# Power_5V_77V.net
KiCad netlist of a schematic drawn in EAGLE
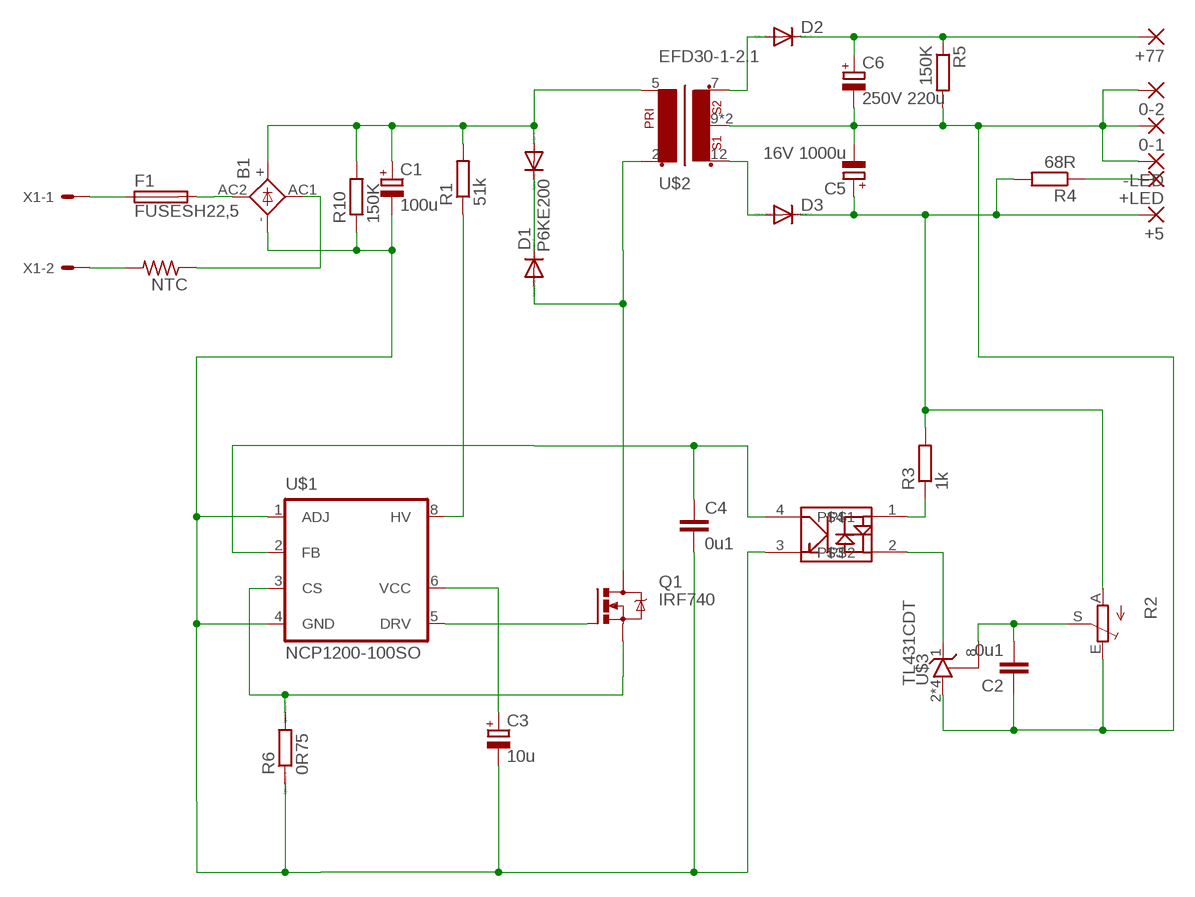
[diagram p0: schematic, sheet 1]

(export (version "E")
  (design (tool "Eeschema 10.0.6"))
  (components
    (comp (ref "+5")
      (value "2,54/0,8")
      (footprint "eagle-import:2,54_0,8")
      (libsource (lib "eagle-import") (part "2,54/0,8"))
    )
    (comp (ref "+77")
      (value "3,17/1,1")
      (footprint "eagle-import:3,17_1,1")
      (libsource (lib "eagle-import") (part "3,17/1,1"))
    )
    (comp (ref "+LED")
      (value "2,54/0,8")
      (footprint "eagle-import:2,54_0,8")
      (libsource (lib "eagle-import") (part "2,54/0,8"))
    )
    (comp (ref "-LED")
      (value "2,54/0,8")
      (footprint "eagle-import:2,54_0,8")
      (libsource (lib "eagle-import") (part "2,54/0,8"))
    )
    (comp (ref "0-1")
      (value "2,54/0,8")
      (footprint "eagle-import:2,54_0,8")
      (libsource (lib "eagle-import") (part "2,54/0,8"))
    )
    (comp (ref "0-2")
      (value "3,17/1,1")
      (footprint "eagle-import:3,17_1,1")
      (libsource (lib "eagle-import") (part "3,17/1,1"))
    )
    (comp (ref "B1")
      (value "KBL")
      (footprint "eagle-import:KBL")
      (libsource (lib "eagle-import") (part "KBL"))
    )
    (comp (ref "C1")
      (value "100u")
      (footprint "eagle-import:EB25D")
      (libsource (lib "eagle-import") (part "CPOL-EUE10-25"))
    )
    (comp (ref "C2")
      (value "0u1")
      (footprint "eagle-import:C1206")
      (libsource (lib "eagle-import") (part "C-EUC1206"))
    )
    (comp (ref "C3")
      (value "10u")
      (footprint "eagle-import:E2,5-5")
      (libsource (lib "eagle-import") (part "CPOL-EUE2.5-5"))
    )
    (comp (ref "C4")
      (value "0u1")
      (footprint "eagle-import:C1206")
      (libsource (lib "eagle-import") (part "C-EUC1206"))
    )
    (comp (ref "C5")
      (value "16V 1000u")
      (footprint "eagle-import:E3,5-8")
      (libsource (lib "eagle-import") (part "CPOL-EUE3.5-8"))
    )
    (comp (ref "C6")
      (value "250V 220u")
      (footprint "eagle-import:EB22,5D")
      (libsource (lib "eagle-import") (part "CPOL-EUE10-22.5"))
    )
    (comp (ref "D1")
      (value "DIODE-DO-214AC")
      (footprint "eagle-import:DO-214AC")
      (libsource (lib "eagle-import") (part "DIODE-DO-214AC"))
    )
    (comp (ref "D2")
      (value "DIODE-TO220V")
      (footprint "eagle-import:TO220ACS")
      (libsource (lib "eagle-import") (part "DIODE-TO220V"))
    )
    (comp (ref "D3")
      (value "DIODE-SMB")
      (footprint "eagle-import:SMB")
      (libsource (lib "eagle-import") (part "DIODE-SMB"))
    )
    (comp (ref "F1")
      (value "FUSESH22,5")
      (footprint "eagle-import:SH22,5")
      (fields (field (name "MF") "SCHURTER") (field (name "MPN") "0031.8201"))
      (libsource (lib "eagle-import") (part "SH22,5"))
    )
    (comp (ref "NTC")
      (value "R-US_0207/10")
      (footprint "eagle-import:0207_10")
      (libsource (lib "eagle-import") (part "R-US_0207/10"))
    )
    (comp (ref "P6KE200")
      (value "DIODE-SMB")
      (footprint "eagle-import:SMB")
      (libsource (lib "eagle-import") (part "DIODE-SMB"))
    )
    (comp (ref "Q1")
      (value "IRF740")
      (footprint "eagle-import:TO220BV")
      (libsource (lib "eagle-import") (part "IRF740"))
    )
    (comp (ref "R1")
      (value "51k")
      (footprint "eagle-import:0922_22")
      (libsource (lib "eagle-import") (part "R-EU_0922/22"))
    )
    (comp (ref "R2")
      (value "TRIM_EU-S75H")
      (footprint "eagle-import:S75H")
      (libsource (lib "eagle-import") (part "TRIM_EU-S75H"))
    )
    (comp (ref "R3")
      (value "1k")
      (footprint "eagle-import:R1206")
      (libsource (lib "eagle-import") (part "R-EU_R1206"))
    )
    (comp (ref "R4")
      (value "68R")
      (footprint "eagle-import:R1206")
      (libsource (lib "eagle-import") (part "R-EU_R1206"))
    )
    (comp (ref "R5")
      (value "150K")
      (footprint "eagle-import:R1206")
      (libsource (lib "eagle-import") (part "R-EU_R1206"))
    )
    (comp (ref "R6")
      (value "0R75")
      (footprint "eagle-import:0411_15")
      (libsource (lib "eagle-import") (part "R-EU_0411_15"))
    )
    (comp (ref "R10")
      (value "150K")
      (footprint "eagle-import:0207_10")
      (libsource (lib "eagle-import") (part "R-EU_0207/10"))
    )
    (comp (ref "U$1")
      (value "NCP1200-100SO")
      (footprint "eagle-import:SOP8")
      (libsource (lib "eagle-import") (part "NCP1200-100SO"))
    )
    (comp (ref "U$2")
      (value "EFD30-1-2.1")
      (footprint "eagle-import:EFD30_1-2.1")
      (libsource (lib "eagle-import") (part "EFD30-1-2.1"))
    )
    (comp (ref "U$3")
      (value "TL431CDT")
      (footprint "eagle-import:SO8")
      (libsource (lib "eagle-import") (part "TL431CDT"))
    )
    (comp (ref "U$5")
      (value "EL3H4(TA)-VG")
      (footprint "eagle-import:SSOP4")
      (libsource (lib "eagle-import") (part "EL3H4(TA)-VG"))
    )
    (comp (ref "X1")
      (value "KK-156-2")
      (footprint "eagle-import:KK-156-2")
      (libsource (lib "eagle-import") (part "KK-156-2"))
    )
  )
  (nets
    (net (code "1") (name "Net-(+5-P)") (class "Default")
      (node (ref "+5") (pin "1") (pinfunction "P_1") (pintype "passive"))
      (node (ref "C5") (pin "+") (pinfunction "+_+") (pintype "passive"))
      (node (ref "D3") (pin "C") (pinfunction "C_C") (pintype "passive"))
      (node (ref "R2") (pin "A") (pinfunction "A_A") (pintype "passive"))
      (node (ref "R3") (pin "2") (pinfunction "2_2") (pintype "passive"))
      (node (ref "R4") (pin "2") (pinfunction "2_2") (pintype "passive"))
    )
    (net (code "2") (name "Net-(+77-P)") (class "Default")
      (node (ref "+77") (pin "1") (pinfunction "P_1") (pintype "passive"))
      (node (ref "C6") (pin "+") (pinfunction "+_+") (pintype "passive"))
      (node (ref "D2") (pin "C") (pinfunction "C_C") (pintype "passive"))
      (node (ref "R5") (pin "1") (pinfunction "1_1") (pintype "passive"))
    )
    (net (code "3") (name "Net-(+LED-P)") (class "Default")
      (node (ref "+LED") (pin "1") (pinfunction "P_1") (pintype "passive"))
      (node (ref "R4") (pin "1") (pinfunction "1_1") (pintype "passive"))
    )
    (net (code "4") (name "Net-(-LED-P)") (class "Default")
      (node (ref "-LED") (pin "1") (pinfunction "P_1") (pintype "passive"))
      (node (ref "0-1") (pin "1") (pinfunction "P_1") (pintype "passive"))
      (node (ref "0-2") (pin "1") (pinfunction "P_1") (pintype "passive"))
      (node (ref "C2") (pin "1") (pinfunction "1_1") (pintype "passive"))
      (node (ref "C5") (pin "-") (pinfunction "-_-") (pintype "passive"))
      (node (ref "C6") (pin "-") (pinfunction "-_-") (pintype "passive"))
      (node (ref "R2") (pin "E") (pinfunction "E_E") (pintype "passive"))
      (node (ref "R5") (pin "2") (pinfunction "2_2") (pintype "passive"))
      (node (ref "U$2") (pin "10") (pinfunction "S0_10") (pintype "passive"))
      (node (ref "U$2") (pin "9") (pinfunction "S0_9") (pintype "passive"))
      (node (ref "U$3") (pin "2") (pinfunction "A_2") (pintype "passive"))
      (node (ref "U$3") (pin "3") (pinfunction "A_3") (pintype "passive"))
      (node (ref "U$3") (pin "6") (pinfunction "A_6") (pintype "passive"))
      (node (ref "U$3") (pin "7") (pinfunction "A_7") (pintype "passive"))
    )
    (net (code "5") (name "Net-(B1-AC1)") (class "Default")
      (node (ref "B1") (pin "AC2") (pinfunction "AC1_AC2") (pintype "passive"))
      (node (ref "F1") (pin "2") (pinfunction "2_2") (pintype "passive"))
    )
    (net (code "6") (name "Net-(B1-AC2)") (class "Default")
      (node (ref "B1") (pin "AC1") (pinfunction "AC2_AC1") (pintype "passive"))
      (node (ref "NTC") (pin "1") (pinfunction "1_1") (pintype "passive"))
    )
    (net (code "7") (name "Net-(D1-PadC)") (class "Default")
      (node (ref "D1") (pin "C") (pinfunction "C_C") (pintype "passive"))
      (node (ref "P6KE200") (pin "C") (pinfunction "C_C") (pintype "passive"))
    )
    (net (code "8") (name "Net-(U$1-ADJ)") (class "Default")
      (node (ref "B1") (pin "-") (pinfunction "-_-") (pintype "passive"))
      (node (ref "C1") (pin "-") (pinfunction "-_-") (pintype "passive"))
      (node (ref "C3") (pin "-") (pinfunction "-_-") (pintype "passive"))
      (node (ref "C4") (pin "2") (pinfunction "2_2") (pintype "passive"))
      (node (ref "R10") (pin "1") (pinfunction "1_1") (pintype "passive"))
      (node (ref "R6") (pin "1") (pinfunction "1_1") (pintype "passive"))
      (node (ref "U$1") (pin "1") (pinfunction "ADJ_1") (pintype "passive"))
      (node (ref "U$1") (pin "4") (pinfunction "GND_4") (pintype "passive"))
      (node (ref "U$5") (pin "3") (pinfunction "P$3_3") (pintype "bidirectional"))
    )
    (net (code "9") (name "Net-(U$1-CS)") (class "Default")
      (node (ref "Q1") (pin "S") (pinfunction "S_S") (pintype "passive"))
      (node (ref "R6") (pin "2") (pinfunction "2_2") (pintype "passive"))
      (node (ref "U$1") (pin "3") (pinfunction "CS_3") (pintype "input"))
    )
    (net (code "10") (name "Net-(U$1-DRV)") (class "Default")
      (node (ref "Q1") (pin "G") (pinfunction "G_G") (pintype "passive"))
      (node (ref "U$1") (pin "5") (pinfunction "DRV_5") (pintype "power_in"))
    )
    (net (code "11") (name "Net-(U$1-FB)") (class "Default")
      (node (ref "C4") (pin "1") (pinfunction "1_1") (pintype "passive"))
      (node (ref "U$1") (pin "2") (pinfunction "FB_2") (pintype "input"))
      (node (ref "U$5") (pin "4") (pinfunction "P$4_4") (pintype "bidirectional"))
    )
    (net (code "12") (name "Net-(U$1-HV)") (class "Default")
      (node (ref "R1") (pin "1") (pinfunction "1_1") (pintype "passive"))
      (node (ref "U$1") (pin "8") (pinfunction "HV_8") (pintype "passive"))
    )
    (net (code "13") (name "Net-(U$1-VCC)") (class "Default")
      (node (ref "C3") (pin "+") (pinfunction "+_+") (pintype "passive"))
      (node (ref "U$1") (pin "6") (pinfunction "VCC_6") (pintype "output"))
    )
    (net (code "14") (name "Net-(U$2-P1-1)") (class "Default")
      (node (ref "D1") (pin "A") (pinfunction "A_A") (pintype "passive"))
      (node (ref "Q1") (pin "D") (pinfunction "D_D") (pintype "passive"))
      (node (ref "U$2") (pin "2") (pinfunction "P1-1_2") (pintype "passive"))
    )
    (net (code "15") (name "Net-(U$2-P1-2)") (class "Default")
      (node (ref "B1") (pin "+") (pinfunction "+_+") (pintype "passive"))
      (node (ref "C1") (pin "+") (pinfunction "+_+") (pintype "passive"))
      (node (ref "P6KE200") (pin "A") (pinfunction "A_A") (pintype "passive"))
      (node (ref "R1") (pin "2") (pinfunction "2_2") (pintype "passive"))
      (node (ref "R10") (pin "2") (pinfunction "2_2") (pintype "passive"))
      (node (ref "U$2") (pin "5") (pinfunction "P1-2_5") (pintype "passive"))
    )
    (net (code "16") (name "Net-(U$2-S1)") (class "Default")
      (node (ref "D3") (pin "A") (pinfunction "A_A") (pintype "passive"))
      (node (ref "U$2") (pin "12") (pinfunction "S1_12") (pintype "passive"))
    )
    (net (code "17") (name "Net-(U$2-S2)") (class "Default")
      (node (ref "D2") (pin "A") (pinfunction "A_A") (pintype "passive"))
      (node (ref "U$2") (pin "7") (pinfunction "S2_7") (pintype "passive"))
    )
    (net (code "18") (name "Net-(U$3-C)") (class "Default")
      (node (ref "U$3") (pin "1") (pinfunction "C_1") (pintype "passive"))
      (node (ref "U$5") (pin "2") (pinfunction "P$2_2") (pintype "bidirectional"))
    )
    (net (code "19") (name "Net-(U$3-R)") (class "Default")
      (node (ref "C2") (pin "2") (pinfunction "2_2") (pintype "passive"))
      (node (ref "R2") (pin "S") (pinfunction "S_S") (pintype "passive"))
      (node (ref "U$3") (pin "8") (pinfunction "R_8") (pintype "passive"))
    )
    (net (code "20") (name "Net-(U$5-P$1)") (class "Default")
      (node (ref "R3") (pin "1") (pinfunction "1_1") (pintype "passive"))
      (node (ref "U$5") (pin "1") (pinfunction "P$1_1") (pintype "bidirectional"))
    )
    (net (code "21") (name "Net-(X1A-S)") (class "Default")
      (node (ref "F1") (pin "1") (pinfunction "1_1") (pintype "passive"))
      (node (ref "X1") (pin "1") (pinfunction "S_1") (pintype "passive"))
    )
    (net (code "22") (name "Net-(X1B-S)") (class "Default")
      (node (ref "NTC") (pin "2") (pinfunction "2_2") (pintype "passive"))
      (node (ref "X1") (pin "2") (pinfunction "S_2") (pintype "passive"))
    )
  )
)
